# Folio01.net
KiCad netlist of a schematic drawn in Altium Designer
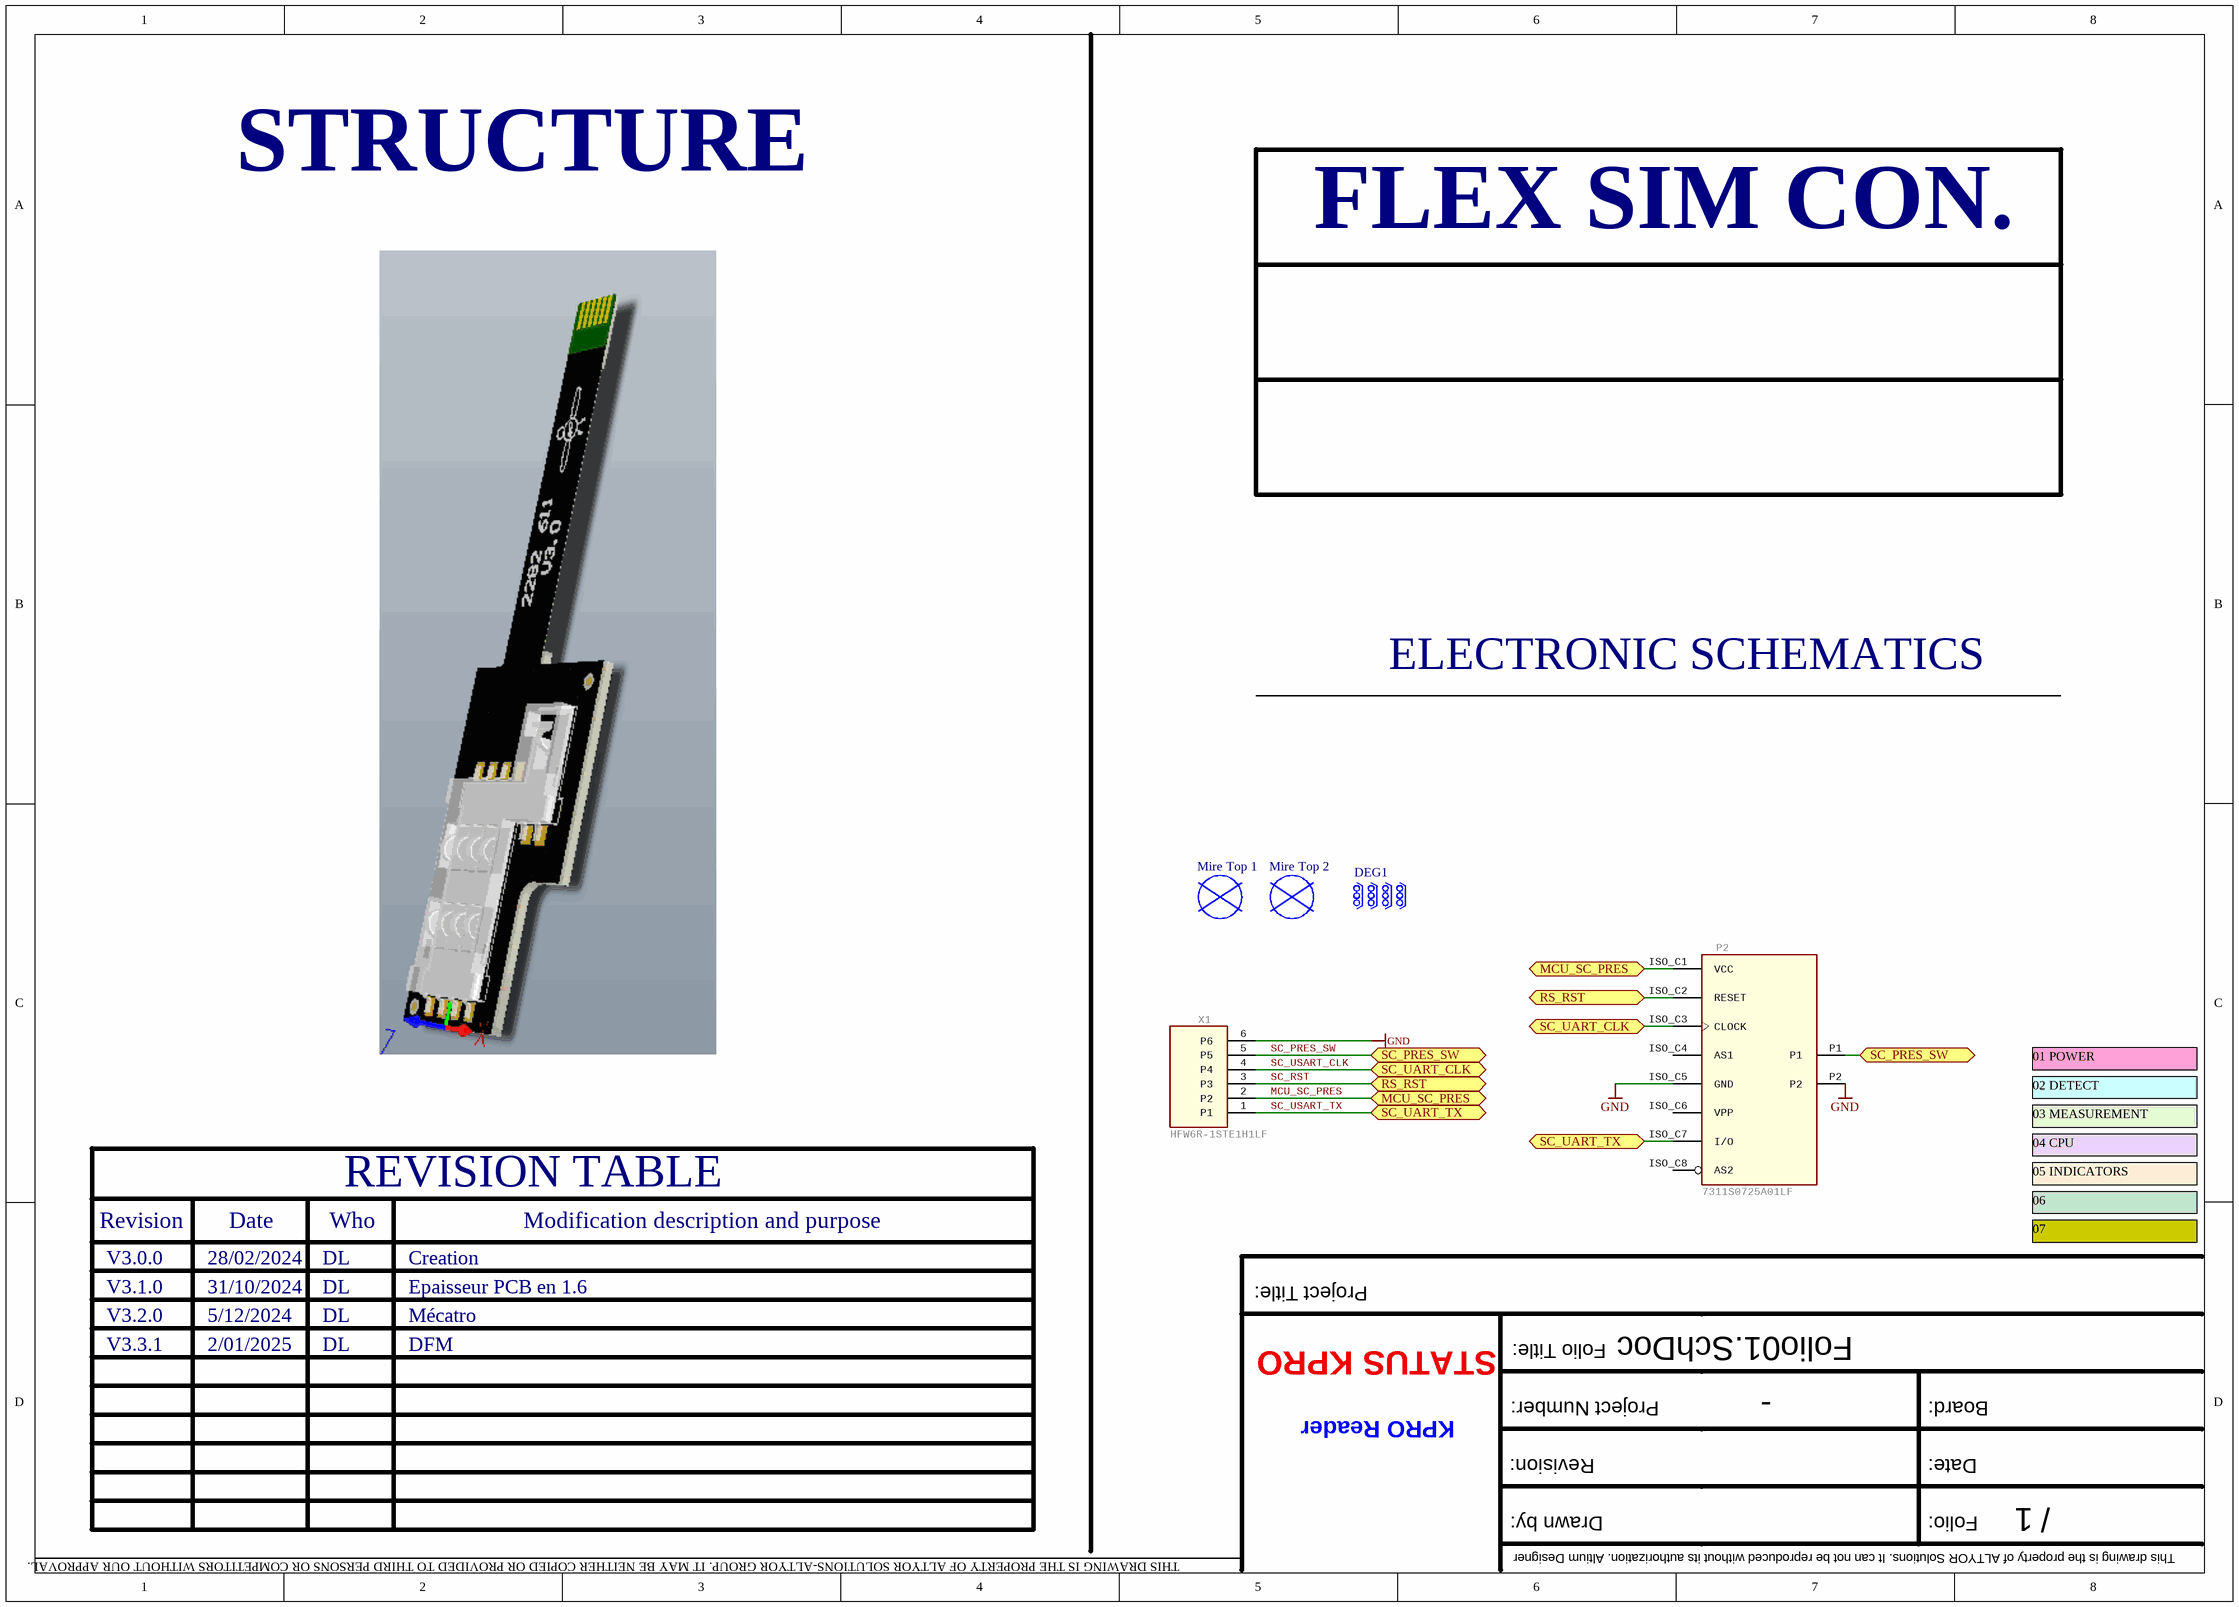
[diagram p0: Folio01.SchDoc]

(export (version "E")
  (design (tool "Eeschema 10.0.6"))
  (components
    (comp (ref "DEG1")
      (value "DNI")
      (footprint "DEGRAPAGE 3 x 0.5")
      (description "Dégrapage (Breakout Tab)")
      (libsource (lib "2376-PCB-600") (part "DEGRAP_3"))
    )
    (comp (ref "DEG2")
      (value "DNI")
      (footprint "DEGRAPAGE 3 x 0.5")
      (description "Dégrapage (Breakout Tab)")
      (libsource (lib "2376-PCB-600") (part "DEGRAP_3"))
    )
    (comp (ref "DEG3")
      (value "DNI")
      (footprint "DEGRAPAGE 3 x 0.5")
      (description "Dégrapage (Breakout Tab)")
      (libsource (lib "2376-PCB-600") (part "DEGRAP_3"))
    )
    (comp (ref "DEG4")
      (value "DNI")
      (footprint "DEGRAPAGE 3 x 0.5")
      (description "Dégrapage (Breakout Tab)")
      (libsource (lib "2376-PCB-600") (part "DEGRAP_3"))
    )
    (comp (ref "Mire Top 1")
      (value "DNI")
      (footprint "MIRE")
      (description "Mire")
      (libsource (lib "PcbLibPDCi - NonValide") (part "Mire"))
    )
    (comp (ref "Mire Top 2")
      (value "DNI")
      (footprint "MIRE")
      (description "Mire")
      (libsource (lib "PcbLibPDCi - NonValide") (part "Mire"))
    )
    (comp (ref "P2")
      (value "7311S0725A01LF")
      (footprint "7311S0725A01LF")
      (description "8 Positions connecteur de carte Micro SIM Montage en surface Ã  angle droit Or avec commutateur")
      (fields (field (name "MANUFACTURER") "AMPHENOL"))
      (libsource (lib "FLX-2282-601") (part "7311S0725A01LF"))
    )
    (comp (ref "X1")
      (value "HFW6R-1STE1H1LF")
      (footprint "FPC_HFW6R-1STE1H1LF")
      (description "Connecteur FCC 6pts 1mm - bottom contect- right angle - 6x1mm")
      (fields (field (name "MANUFACTURER") "AMPHENOL"))
      (libsource (lib "FLX-2282-601") (part "FPC_HFW6R-1STE1H1LF"))
    )
  )
  (nets
    (net (code "1") (name "/MCU_SC_PRES") (class "Default")
      (node (ref "P2") (pin "ISO_C1") (pinfunction "VCC_ISO_C1") (pintype "passive"))
      (node (ref "X1") (pin "2") (pinfunction "P2_2") (pintype "passive"))
    )
    (net (code "2") (name "/SC_PRES_SW") (class "Default")
      (node (ref "P2") (pin "P1") (pinfunction "P1_P1") (pintype "passive"))
      (node (ref "X1") (pin "5") (pinfunction "P5_5") (pintype "passive"))
    )
    (net (code "3") (name "/SC_RST") (class "Default")
      (node (ref "P2") (pin "ISO_C2") (pinfunction "RESET_ISO_C2") (pintype "passive"))
      (node (ref "X1") (pin "3") (pinfunction "P3_3") (pintype "passive"))
    )
    (net (code "4") (name "/SC_USART_CLK") (class "Default")
      (node (ref "P2") (pin "ISO_C3") (pinfunction "CLOCK_ISO_C3") (pintype "passive"))
      (node (ref "X1") (pin "4") (pinfunction "P4_4") (pintype "passive"))
    )
    (net (code "5") (name "/SC_USART_TX") (class "Default")
      (node (ref "P2") (pin "ISO_C7") (pinfunction "I/O_ISO_C7") (pintype "passive"))
      (node (ref "X1") (pin "1") (pinfunction "P1_1") (pintype "passive"))
    )
    (net (code "6") (name "GND") (class "Default")
      (node (ref "P2") (pin "ISO_C5") (pinfunction "GND_ISO_C5") (pintype "passive"))
      (node (ref "P2") (pin "P2") (pinfunction "P2_P2") (pintype "passive"))
      (node (ref "X1") (pin "6") (pinfunction "P6_6") (pintype "passive"))
    )
    (net (code "7") (name "unconnected-(P2-AS1-PadISO_C4)") (class "Default")
      (node (ref "P2") (pin "ISO_C4") (pinfunction "AS1_ISO_C4") (pintype "passive"))
    )
    (net (code "8") (name "unconnected-(P2-AS2-PadISO_C8)") (class "Default")
      (node (ref "P2") (pin "ISO_C8") (pinfunction "AS2_ISO_C8") (pintype "passive"))
    )
    (net (code "9") (name "unconnected-(P2-VPP-PadISO_C6)") (class "Default")
      (node (ref "P2") (pin "ISO_C6") (pinfunction "VPP_ISO_C6") (pintype "passive"))
    )
  )
)
